# LedPot.net
KiCad netlist of a schematic drawn in Altium Designer
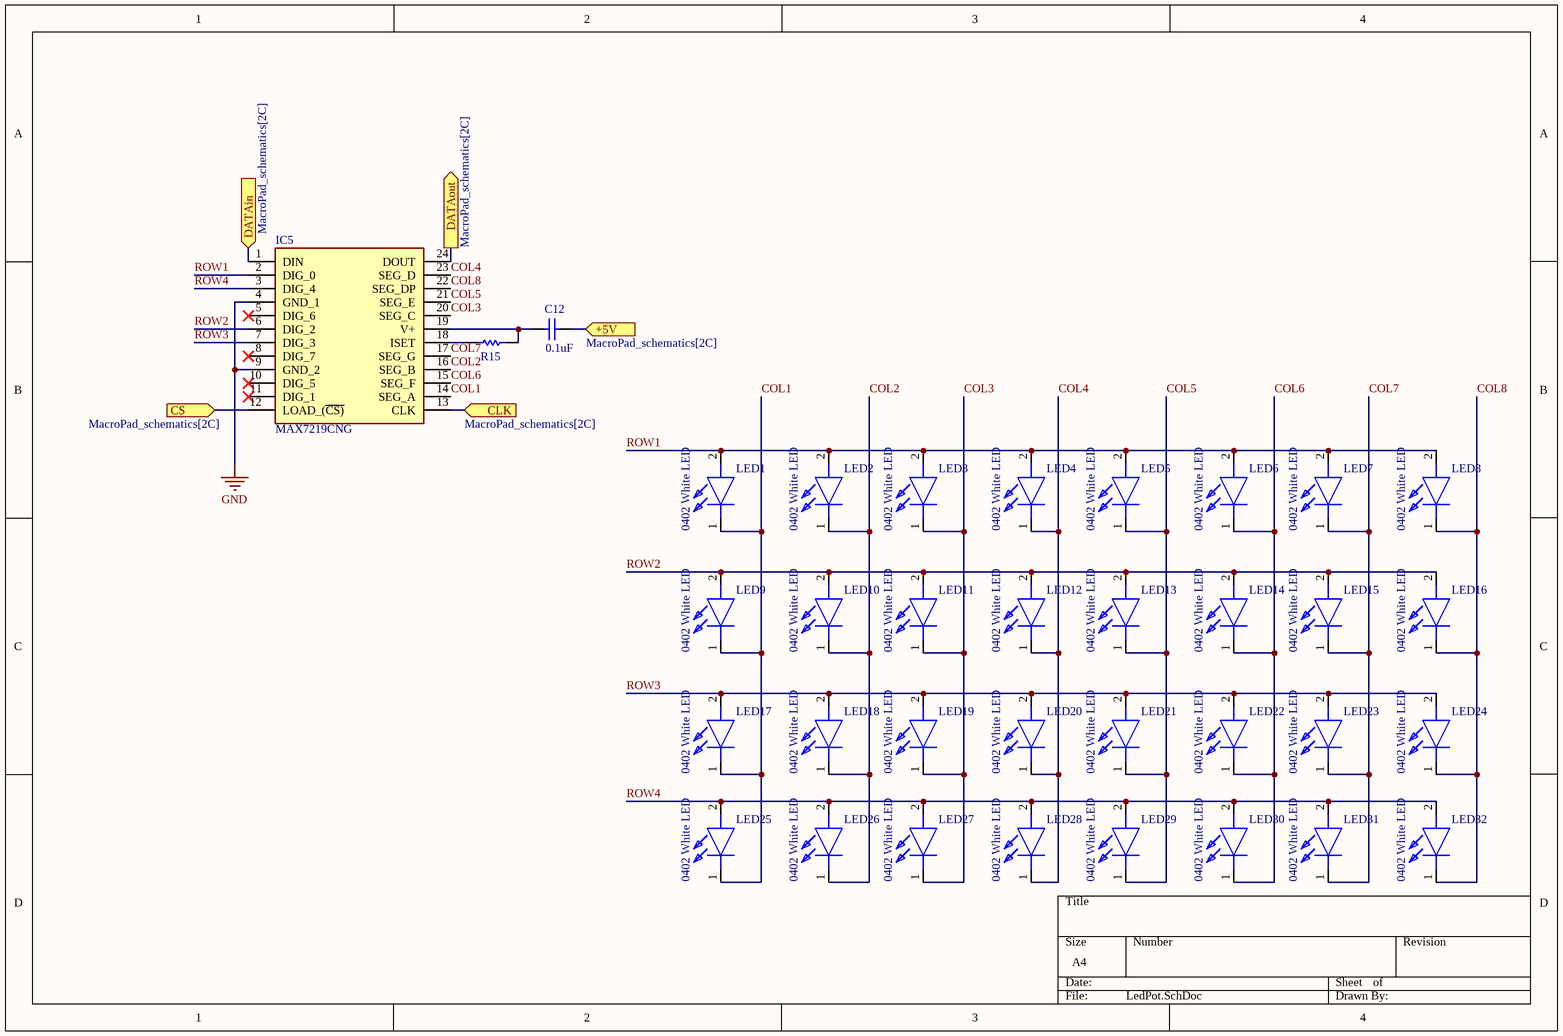
[diagram p0: LedPot.SchDoc]

(export (version "E")
  (design (tool "Eeschema 10.0.6"))
  (components
    (comp (ref "C12")
      (value "0.1uF")
      (footprint "KEMT-1206-2_L")
      (description "General Purpose Capacitor")
      (fields (field (name "TOLERANCE") "10%") (field (name "Comment") "1206 Capacitor"))
      (libsource (lib "EPFL Racing Team") (part "CAP"))
    )
    (comp (ref "IC5")
      (value "MAX7219CNG")
      (footprint "SamacSys:DIP794W56P254L3054H457Q24N")
      (description "Integrated Circuit")
      (fields (field (name "MOUSER PART NUMBER") "700-MAX7219CNG-NR"))
      (libsource (lib "*") (part "MAX7219CNG"))
    )
    (comp (ref "LED1")
      (value "0402 White LED")
      (footprint "SamacSys:LWVH8GQ2OO4M6N1")
      (description "LED")
      (fields
        (field (name "MANUFACTURER_PART_NUMBER") "LW VH8G-Q2OO-4M6N-1")
        (field (name "MOUSER PART NUMBER") "720-LWVH8G-Q2S24M6N1")
      )
      (libsource (lib "*") (part "LW_VH8G-Q2OO-4M6N-1"))
    )
    (comp (ref "LED2")
      (value "0402 White LED")
      (footprint "SamacSys:LWVH8GQ2OO4M6N1")
      (description "LED")
      (fields
        (field (name "MANUFACTURER_PART_NUMBER") "LW VH8G-Q2OO-4M6N-1")
        (field (name "MOUSER PART NUMBER") "720-LWVH8G-Q2S24M6N1")
      )
      (libsource (lib "*") (part "LW_VH8G-Q2OO-4M6N-1"))
    )
    (comp (ref "LED3")
      (value "0402 White LED")
      (footprint "SamacSys:LWVH8GQ2OO4M6N1")
      (description "LED")
      (fields
        (field (name "MANUFACTURER_PART_NUMBER") "LW VH8G-Q2OO-4M6N-1")
        (field (name "MOUSER PART NUMBER") "720-LWVH8G-Q2S24M6N1")
      )
      (libsource (lib "*") (part "LW_VH8G-Q2OO-4M6N-1"))
    )
    (comp (ref "LED4")
      (value "0402 White LED")
      (footprint "SamacSys:LWVH8GQ2OO4M6N1")
      (description "LED")
      (fields
        (field (name "MANUFACTURER_PART_NUMBER") "LW VH8G-Q2OO-4M6N-1")
        (field (name "MOUSER PART NUMBER") "720-LWVH8G-Q2S24M6N1")
      )
      (libsource (lib "*") (part "LW_VH8G-Q2OO-4M6N-1"))
    )
    (comp (ref "LED5")
      (value "0402 White LED")
      (footprint "SamacSys:LWVH8GQ2OO4M6N1")
      (description "LED")
      (fields
        (field (name "MANUFACTURER_PART_NUMBER") "LW VH8G-Q2OO-4M6N-1")
        (field (name "MOUSER PART NUMBER") "720-LWVH8G-Q2S24M6N1")
      )
      (libsource (lib "*") (part "LW_VH8G-Q2OO-4M6N-1"))
    )
    (comp (ref "LED6")
      (value "0402 White LED")
      (footprint "SamacSys:LWVH8GQ2OO4M6N1")
      (description "LED")
      (fields
        (field (name "MANUFACTURER_PART_NUMBER") "LW VH8G-Q2OO-4M6N-1")
        (field (name "MOUSER PART NUMBER") "720-LWVH8G-Q2S24M6N1")
      )
      (libsource (lib "*") (part "LW_VH8G-Q2OO-4M6N-1"))
    )
    (comp (ref "LED7")
      (value "0402 White LED")
      (footprint "SamacSys:LWVH8GQ2OO4M6N1")
      (description "LED")
      (fields
        (field (name "MANUFACTURER_PART_NUMBER") "LW VH8G-Q2OO-4M6N-1")
        (field (name "MOUSER PART NUMBER") "720-LWVH8G-Q2S24M6N1")
      )
      (libsource (lib "*") (part "LW_VH8G-Q2OO-4M6N-1"))
    )
    (comp (ref "LED8")
      (value "0402 White LED")
      (footprint "SamacSys:LWVH8GQ2OO4M6N1")
      (description "LED")
      (fields
        (field (name "MANUFACTURER_PART_NUMBER") "LW VH8G-Q2OO-4M6N-1")
        (field (name "MOUSER PART NUMBER") "720-LWVH8G-Q2S24M6N1")
      )
      (libsource (lib "*") (part "LW_VH8G-Q2OO-4M6N-1"))
    )
    (comp (ref "LED9")
      (value "0402 White LED")
      (footprint "SamacSys:LWVH8GQ2OO4M6N1")
      (description "LED")
      (fields
        (field (name "MANUFACTURER_PART_NUMBER") "LW VH8G-Q2OO-4M6N-1")
        (field (name "MOUSER PART NUMBER") "720-LWVH8G-Q2S24M6N1")
      )
      (libsource (lib "*") (part "LW_VH8G-Q2OO-4M6N-1"))
    )
    (comp (ref "LED10")
      (value "0402 White LED")
      (footprint "SamacSys:LWVH8GQ2OO4M6N1")
      (description "LED")
      (fields
        (field (name "MANUFACTURER_PART_NUMBER") "LW VH8G-Q2OO-4M6N-1")
        (field (name "MOUSER PART NUMBER") "720-LWVH8G-Q2S24M6N1")
      )
      (libsource (lib "*") (part "LW_VH8G-Q2OO-4M6N-1"))
    )
    (comp (ref "LED11")
      (value "0402 White LED")
      (footprint "SamacSys:LWVH8GQ2OO4M6N1")
      (description "LED")
      (fields
        (field (name "MANUFACTURER_PART_NUMBER") "LW VH8G-Q2OO-4M6N-1")
        (field (name "MOUSER PART NUMBER") "720-LWVH8G-Q2S24M6N1")
      )
      (libsource (lib "*") (part "LW_VH8G-Q2OO-4M6N-1"))
    )
    (comp (ref "LED12")
      (value "0402 White LED")
      (footprint "SamacSys:LWVH8GQ2OO4M6N1")
      (description "LED")
      (fields
        (field (name "MANUFACTURER_PART_NUMBER") "LW VH8G-Q2OO-4M6N-1")
        (field (name "MOUSER PART NUMBER") "720-LWVH8G-Q2S24M6N1")
      )
      (libsource (lib "*") (part "LW_VH8G-Q2OO-4M6N-1"))
    )
    (comp (ref "LED13")
      (value "0402 White LED")
      (footprint "SamacSys:LWVH8GQ2OO4M6N1")
      (description "LED")
      (fields
        (field (name "MANUFACTURER_PART_NUMBER") "LW VH8G-Q2OO-4M6N-1")
        (field (name "MOUSER PART NUMBER") "720-LWVH8G-Q2S24M6N1")
      )
      (libsource (lib "*") (part "LW_VH8G-Q2OO-4M6N-1"))
    )
    (comp (ref "LED14")
      (value "0402 White LED")
      (footprint "SamacSys:LWVH8GQ2OO4M6N1")
      (description "LED")
      (fields
        (field (name "MANUFACTURER_PART_NUMBER") "LW VH8G-Q2OO-4M6N-1")
        (field (name "MOUSER PART NUMBER") "720-LWVH8G-Q2S24M6N1")
      )
      (libsource (lib "*") (part "LW_VH8G-Q2OO-4M6N-1"))
    )
    (comp (ref "LED15")
      (value "0402 White LED")
      (footprint "SamacSys:LWVH8GQ2OO4M6N1")
      (description "LED")
      (fields
        (field (name "MANUFACTURER_PART_NUMBER") "LW VH8G-Q2OO-4M6N-1")
        (field (name "MOUSER PART NUMBER") "720-LWVH8G-Q2S24M6N1")
      )
      (libsource (lib "*") (part "LW_VH8G-Q2OO-4M6N-1"))
    )
    (comp (ref "LED16")
      (value "0402 White LED")
      (footprint "SamacSys:LWVH8GQ2OO4M6N1")
      (description "LED")
      (fields
        (field (name "MANUFACTURER_PART_NUMBER") "LW VH8G-Q2OO-4M6N-1")
        (field (name "MOUSER PART NUMBER") "720-LWVH8G-Q2S24M6N1")
      )
      (libsource (lib "*") (part "LW_VH8G-Q2OO-4M6N-1"))
    )
    (comp (ref "LED17")
      (value "0402 White LED")
      (footprint "SamacSys:LWVH8GQ2OO4M6N1")
      (description "LED")
      (fields
        (field (name "MANUFACTURER_PART_NUMBER") "LW VH8G-Q2OO-4M6N-1")
        (field (name "MOUSER PART NUMBER") "720-LWVH8G-Q2S24M6N1")
      )
      (libsource (lib "*") (part "LW_VH8G-Q2OO-4M6N-1"))
    )
    (comp (ref "LED18")
      (value "0402 White LED")
      (footprint "SamacSys:LWVH8GQ2OO4M6N1")
      (description "LED")
      (fields
        (field (name "MANUFACTURER_PART_NUMBER") "LW VH8G-Q2OO-4M6N-1")
        (field (name "MOUSER PART NUMBER") "720-LWVH8G-Q2S24M6N1")
      )
      (libsource (lib "*") (part "LW_VH8G-Q2OO-4M6N-1"))
    )
    (comp (ref "LED19")
      (value "0402 White LED")
      (footprint "SamacSys:LWVH8GQ2OO4M6N1")
      (description "LED")
      (fields
        (field (name "MANUFACTURER_PART_NUMBER") "LW VH8G-Q2OO-4M6N-1")
        (field (name "MOUSER PART NUMBER") "720-LWVH8G-Q2S24M6N1")
      )
      (libsource (lib "*") (part "LW_VH8G-Q2OO-4M6N-1"))
    )
    (comp (ref "LED20")
      (value "0402 White LED")
      (footprint "SamacSys:LWVH8GQ2OO4M6N1")
      (description "LED")
      (fields
        (field (name "MANUFACTURER_PART_NUMBER") "LW VH8G-Q2OO-4M6N-1")
        (field (name "MOUSER PART NUMBER") "720-LWVH8G-Q2S24M6N1")
      )
      (libsource (lib "*") (part "LW_VH8G-Q2OO-4M6N-1"))
    )
    (comp (ref "LED21")
      (value "0402 White LED")
      (footprint "SamacSys:LWVH8GQ2OO4M6N1")
      (description "LED")
      (fields
        (field (name "MANUFACTURER_PART_NUMBER") "LW VH8G-Q2OO-4M6N-1")
        (field (name "MOUSER PART NUMBER") "720-LWVH8G-Q2S24M6N1")
      )
      (libsource (lib "*") (part "LW_VH8G-Q2OO-4M6N-1"))
    )
    (comp (ref "LED22")
      (value "0402 White LED")
      (footprint "SamacSys:LWVH8GQ2OO4M6N1")
      (description "LED")
      (fields
        (field (name "MANUFACTURER_PART_NUMBER") "LW VH8G-Q2OO-4M6N-1")
        (field (name "MOUSER PART NUMBER") "720-LWVH8G-Q2S24M6N1")
      )
      (libsource (lib "*") (part "LW_VH8G-Q2OO-4M6N-1"))
    )
    (comp (ref "LED23")
      (value "0402 White LED")
      (footprint "SamacSys:LWVH8GQ2OO4M6N1")
      (description "LED")
      (fields
        (field (name "MANUFACTURER_PART_NUMBER") "LW VH8G-Q2OO-4M6N-1")
        (field (name "MOUSER PART NUMBER") "720-LWVH8G-Q2S24M6N1")
      )
      (libsource (lib "*") (part "LW_VH8G-Q2OO-4M6N-1"))
    )
    (comp (ref "LED24")
      (value "0402 White LED")
      (footprint "SamacSys:LWVH8GQ2OO4M6N1")
      (description "LED")
      (fields
        (field (name "MANUFACTURER_PART_NUMBER") "LW VH8G-Q2OO-4M6N-1")
        (field (name "MOUSER PART NUMBER") "720-LWVH8G-Q2S24M6N1")
      )
      (libsource (lib "*") (part "LW_VH8G-Q2OO-4M6N-1"))
    )
    (comp (ref "LED25")
      (value "0402 White LED")
      (footprint "SamacSys:LWVH8GQ2OO4M6N1")
      (description "LED")
      (fields
        (field (name "MANUFACTURER_PART_NUMBER") "LW VH8G-Q2OO-4M6N-1")
        (field (name "MOUSER PART NUMBER") "720-LWVH8G-Q2S24M6N1")
      )
      (libsource (lib "*") (part "LW_VH8G-Q2OO-4M6N-1"))
    )
    (comp (ref "LED26")
      (value "0402 White LED")
      (footprint "SamacSys:LWVH8GQ2OO4M6N1")
      (description "LED")
      (fields
        (field (name "MANUFACTURER_PART_NUMBER") "LW VH8G-Q2OO-4M6N-1")
        (field (name "MOUSER PART NUMBER") "720-LWVH8G-Q2S24M6N1")
      )
      (libsource (lib "*") (part "LW_VH8G-Q2OO-4M6N-1"))
    )
    (comp (ref "LED27")
      (value "0402 White LED")
      (footprint "SamacSys:LWVH8GQ2OO4M6N1")
      (description "LED")
      (fields
        (field (name "MANUFACTURER_PART_NUMBER") "LW VH8G-Q2OO-4M6N-1")
        (field (name "MOUSER PART NUMBER") "720-LWVH8G-Q2S24M6N1")
      )
      (libsource (lib "*") (part "LW_VH8G-Q2OO-4M6N-1"))
    )
    (comp (ref "LED28")
      (value "0402 White LED")
      (footprint "SamacSys:LWVH8GQ2OO4M6N1")
      (description "LED")
      (fields
        (field (name "MANUFACTURER_PART_NUMBER") "LW VH8G-Q2OO-4M6N-1")
        (field (name "MOUSER PART NUMBER") "720-LWVH8G-Q2S24M6N1")
      )
      (libsource (lib "*") (part "LW_VH8G-Q2OO-4M6N-1"))
    )
    (comp (ref "LED29")
      (value "0402 White LED")
      (footprint "SamacSys:LWVH8GQ2OO4M6N1")
      (description "LED")
      (fields
        (field (name "MANUFACTURER_PART_NUMBER") "LW VH8G-Q2OO-4M6N-1")
        (field (name "MOUSER PART NUMBER") "720-LWVH8G-Q2S24M6N1")
      )
      (libsource (lib "*") (part "LW_VH8G-Q2OO-4M6N-1"))
    )
    (comp (ref "LED30")
      (value "0402 White LED")
      (footprint "SamacSys:LWVH8GQ2OO4M6N1")
      (description "LED")
      (fields
        (field (name "MANUFACTURER_PART_NUMBER") "LW VH8G-Q2OO-4M6N-1")
        (field (name "MOUSER PART NUMBER") "720-LWVH8G-Q2S24M6N1")
      )
      (libsource (lib "*") (part "LW_VH8G-Q2OO-4M6N-1"))
    )
    (comp (ref "LED31")
      (value "0402 White LED")
      (footprint "SamacSys:LWVH8GQ2OO4M6N1")
      (description "LED")
      (fields
        (field (name "MANUFACTURER_PART_NUMBER") "LW VH8G-Q2OO-4M6N-1")
        (field (name "MOUSER PART NUMBER") "720-LWVH8G-Q2S24M6N1")
      )
      (libsource (lib "*") (part "LW_VH8G-Q2OO-4M6N-1"))
    )
    (comp (ref "LED32")
      (value "0402 White LED")
      (footprint "SamacSys:LWVH8GQ2OO4M6N1")
      (description "LED")
      (fields
        (field (name "MANUFACTURER_PART_NUMBER") "LW VH8G-Q2OO-4M6N-1")
        (field (name "MOUSER PART NUMBER") "720-LWVH8G-Q2S24M6N1")
      )
      (libsource (lib "*") (part "LW_VH8G-Q2OO-4M6N-1"))
    )
    (comp (ref "R15")
      (value "0402 Resistor")
      (footprint "RESC1005X40X25ML05T05")
      (description "General Purpose 0402 Resistor")
      (fields (field (name "TOLERANCE") "1%"))
      (libsource (lib "EPFL Racing Team") (part "RES-2"))
    )
  )
  (nets
    (net (code "1") (name "/+5V") (class "Default")
      (node (ref "C12") (pin "2") (pinfunction "2_2") (pintype "passive"))
    )
    (net (code "2") (name "/CLK") (class "Default")
      (node (ref "IC5") (pin "13") (pinfunction "CLK_13") (pintype "passive"))
    )
    (net (code "3") (name "/COL1") (class "Default")
      (node (ref "IC5") (pin "14") (pinfunction "SEG_A_14") (pintype "passive"))
      (node (ref "LED1") (pin "1") (pinfunction "K_1") (pintype "passive"))
      (node (ref "LED17") (pin "1") (pinfunction "K_1") (pintype "passive"))
      (node (ref "LED25") (pin "1") (pinfunction "K_1") (pintype "passive"))
      (node (ref "LED9") (pin "1") (pinfunction "K_1") (pintype "passive"))
    )
    (net (code "4") (name "/COL2") (class "Default")
      (node (ref "IC5") (pin "16") (pinfunction "SEG_B_16") (pintype "passive"))
      (node (ref "LED10") (pin "1") (pinfunction "K_1") (pintype "passive"))
      (node (ref "LED18") (pin "1") (pinfunction "K_1") (pintype "passive"))
      (node (ref "LED2") (pin "1") (pinfunction "K_1") (pintype "passive"))
      (node (ref "LED26") (pin "1") (pinfunction "K_1") (pintype "passive"))
    )
    (net (code "5") (name "/COL3") (class "Default")
      (node (ref "IC5") (pin "20") (pinfunction "SEG_C_20") (pintype "passive"))
      (node (ref "LED11") (pin "1") (pinfunction "K_1") (pintype "passive"))
      (node (ref "LED19") (pin "1") (pinfunction "K_1") (pintype "passive"))
      (node (ref "LED27") (pin "1") (pinfunction "K_1") (pintype "passive"))
      (node (ref "LED3") (pin "1") (pinfunction "K_1") (pintype "passive"))
    )
    (net (code "6") (name "/COL4") (class "Default")
      (node (ref "IC5") (pin "23") (pinfunction "SEG_D_23") (pintype "passive"))
      (node (ref "LED12") (pin "1") (pinfunction "K_1") (pintype "passive"))
      (node (ref "LED20") (pin "1") (pinfunction "K_1") (pintype "passive"))
      (node (ref "LED28") (pin "1") (pinfunction "K_1") (pintype "passive"))
      (node (ref "LED4") (pin "1") (pinfunction "K_1") (pintype "passive"))
    )
    (net (code "7") (name "/COL5") (class "Default")
      (node (ref "IC5") (pin "21") (pinfunction "SEG_E_21") (pintype "passive"))
      (node (ref "LED13") (pin "1") (pinfunction "K_1") (pintype "passive"))
      (node (ref "LED21") (pin "1") (pinfunction "K_1") (pintype "passive"))
      (node (ref "LED29") (pin "1") (pinfunction "K_1") (pintype "passive"))
      (node (ref "LED5") (pin "1") (pinfunction "K_1") (pintype "passive"))
    )
    (net (code "8") (name "/COL6") (class "Default")
      (node (ref "IC5") (pin "15") (pinfunction "SEG_F_15") (pintype "passive"))
      (node (ref "LED14") (pin "1") (pinfunction "K_1") (pintype "passive"))
      (node (ref "LED22") (pin "1") (pinfunction "K_1") (pintype "passive"))
      (node (ref "LED30") (pin "1") (pinfunction "K_1") (pintype "passive"))
      (node (ref "LED6") (pin "1") (pinfunction "K_1") (pintype "passive"))
    )
    (net (code "9") (name "/COL7") (class "Default")
      (node (ref "IC5") (pin "17") (pinfunction "SEG_G_17") (pintype "passive"))
      (node (ref "LED15") (pin "1") (pinfunction "K_1") (pintype "passive"))
      (node (ref "LED23") (pin "1") (pinfunction "K_1") (pintype "passive"))
      (node (ref "LED31") (pin "1") (pinfunction "K_1") (pintype "passive"))
      (node (ref "LED7") (pin "1") (pinfunction "K_1") (pintype "passive"))
    )
    (net (code "10") (name "/COL8") (class "Default")
      (node (ref "IC5") (pin "22") (pinfunction "SEG_DP_22") (pintype "passive"))
      (node (ref "LED16") (pin "1") (pinfunction "K_1") (pintype "passive"))
      (node (ref "LED24") (pin "1") (pinfunction "K_1") (pintype "passive"))
      (node (ref "LED32") (pin "1") (pinfunction "K_1") (pintype "passive"))
      (node (ref "LED8") (pin "1") (pinfunction "K_1") (pintype "passive"))
    )
    (net (code "11") (name "/CS") (class "Default")
      (node (ref "IC5") (pin "12") (pinfunction "LOAD_(~{CS)}_12") (pintype "passive"))
    )
    (net (code "12") (name "/DATAin") (class "Default")
      (node (ref "IC5") (pin "1") (pinfunction "DIN_1") (pintype "passive"))
    )
    (net (code "13") (name "/DATAout") (class "Default")
      (node (ref "IC5") (pin "24") (pinfunction "DOUT_24") (pintype "passive"))
    )
    (net (code "14") (name "/ROW1") (class "Default")
      (node (ref "IC5") (pin "2") (pinfunction "DIG_0_2") (pintype "passive"))
      (node (ref "LED1") (pin "2") (pinfunction "A_2") (pintype "passive"))
      (node (ref "LED2") (pin "2") (pinfunction "A_2") (pintype "passive"))
      (node (ref "LED3") (pin "2") (pinfunction "A_2") (pintype "passive"))
      (node (ref "LED4") (pin "2") (pinfunction "A_2") (pintype "passive"))
      (node (ref "LED5") (pin "2") (pinfunction "A_2") (pintype "passive"))
      (node (ref "LED6") (pin "2") (pinfunction "A_2") (pintype "passive"))
      (node (ref "LED7") (pin "2") (pinfunction "A_2") (pintype "passive"))
      (node (ref "LED8") (pin "2") (pinfunction "A_2") (pintype "passive"))
    )
    (net (code "15") (name "/ROW2") (class "Default")
      (node (ref "IC5") (pin "6") (pinfunction "DIG_2_6") (pintype "passive"))
      (node (ref "LED10") (pin "2") (pinfunction "A_2") (pintype "passive"))
      (node (ref "LED11") (pin "2") (pinfunction "A_2") (pintype "passive"))
      (node (ref "LED12") (pin "2") (pinfunction "A_2") (pintype "passive"))
      (node (ref "LED13") (pin "2") (pinfunction "A_2") (pintype "passive"))
      (node (ref "LED14") (pin "2") (pinfunction "A_2") (pintype "passive"))
      (node (ref "LED15") (pin "2") (pinfunction "A_2") (pintype "passive"))
      (node (ref "LED16") (pin "2") (pinfunction "A_2") (pintype "passive"))
      (node (ref "LED9") (pin "2") (pinfunction "A_2") (pintype "passive"))
    )
    (net (code "16") (name "/ROW3") (class "Default")
      (node (ref "IC5") (pin "7") (pinfunction "DIG_3_7") (pintype "passive"))
      (node (ref "LED17") (pin "2") (pinfunction "A_2") (pintype "passive"))
      (node (ref "LED18") (pin "2") (pinfunction "A_2") (pintype "passive"))
      (node (ref "LED19") (pin "2") (pinfunction "A_2") (pintype "passive"))
      (node (ref "LED20") (pin "2") (pinfunction "A_2") (pintype "passive"))
      (node (ref "LED21") (pin "2") (pinfunction "A_2") (pintype "passive"))
      (node (ref "LED22") (pin "2") (pinfunction "A_2") (pintype "passive"))
      (node (ref "LED23") (pin "2") (pinfunction "A_2") (pintype "passive"))
      (node (ref "LED24") (pin "2") (pinfunction "A_2") (pintype "passive"))
    )
    (net (code "17") (name "/ROW4") (class "Default")
      (node (ref "IC5") (pin "3") (pinfunction "DIG_4_3") (pintype "passive"))
      (node (ref "LED25") (pin "2") (pinfunction "A_2") (pintype "passive"))
      (node (ref "LED26") (pin "2") (pinfunction "A_2") (pintype "passive"))
      (node (ref "LED27") (pin "2") (pinfunction "A_2") (pintype "passive"))
      (node (ref "LED28") (pin "2") (pinfunction "A_2") (pintype "passive"))
      (node (ref "LED29") (pin "2") (pinfunction "A_2") (pintype "passive"))
      (node (ref "LED30") (pin "2") (pinfunction "A_2") (pintype "passive"))
      (node (ref "LED31") (pin "2") (pinfunction "A_2") (pintype "passive"))
      (node (ref "LED32") (pin "2") (pinfunction "A_2") (pintype "passive"))
    )
    (net (code "18") (name "GND") (class "Default")
      (node (ref "IC5") (pin "4") (pinfunction "GND_1_4") (pintype "passive"))
      (node (ref "IC5") (pin "9") (pinfunction "GND_2_9") (pintype "passive"))
    )
    (net (code "19") (name "Net-(IC5-ISET)") (class "Default")
      (node (ref "IC5") (pin "18") (pinfunction "ISET_18") (pintype "passive"))
      (node (ref "R15") (pin "1") (pinfunction "1_1") (pintype "passive"))
    )
    (net (code "20") (name "Net-(IC5-V+)") (class "Default")
      (node (ref "C12") (pin "1") (pinfunction "1_1") (pintype "passive"))
      (node (ref "IC5") (pin "19") (pinfunction "V+_19") (pintype "passive"))
      (node (ref "R15") (pin "2") (pinfunction "2_2") (pintype "passive"))
    )
    (net (code "21") (name "unconnected-(IC5-DIG_1-Pad11)") (class "Default")
      (node (ref "IC5") (pin "11") (pinfunction "DIG_1_11") (pintype "passive+no_connect"))
    )
    (net (code "22") (name "unconnected-(IC5-DIG_5-Pad10)") (class "Default")
      (node (ref "IC5") (pin "10") (pinfunction "DIG_5_10") (pintype "passive+no_connect"))
    )
    (net (code "23") (name "unconnected-(IC5-DIG_6-Pad5)") (class "Default")
      (node (ref "IC5") (pin "5") (pinfunction "DIG_6_5") (pintype "passive+no_connect"))
    )
    (net (code "24") (name "unconnected-(IC5-DIG_7-Pad8)") (class "Default")
      (node (ref "IC5") (pin "8") (pinfunction "DIG_7_8") (pintype "passive+no_connect"))
    )
  )
)
